# Si4356-V1.net
KiCad netlist of a schematic drawn in EAGLE
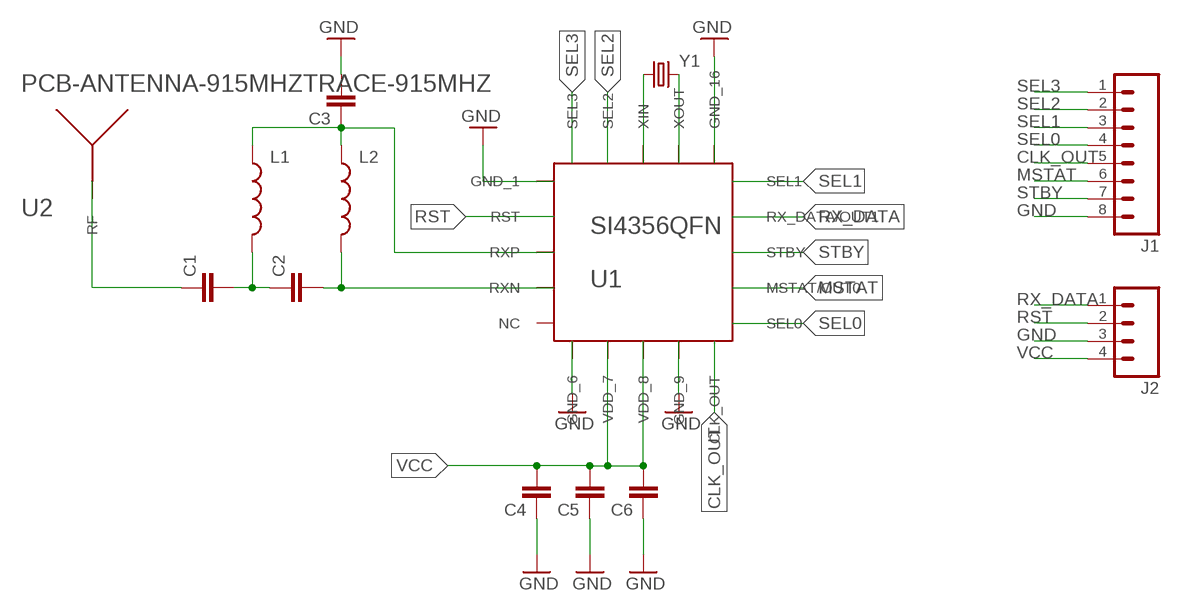
[diagram p0: schematic, sheet 1]

(export (version "E")
  (design (tool "Eeschema 10.0.6"))
  (components
    (comp (ref "C1")
      (value "CAP0603-CAP")
      (footprint "eagle-import:0603-CAP")
      (libsource (lib "eagle-import") (part "CAP0603-CAP"))
    )
    (comp (ref "C2")
      (value "CAP0603-CAP")
      (footprint "eagle-import:0603-CAP")
      (libsource (lib "eagle-import") (part "CAP0603-CAP"))
    )
    (comp (ref "C3")
      (value "CAP0603-CAP")
      (footprint "eagle-import:0603-CAP")
      (libsource (lib "eagle-import") (part "CAP0603-CAP"))
    )
    (comp (ref "C4")
      (value "CAP0603-CAP")
      (footprint "eagle-import:0603-CAP")
      (libsource (lib "eagle-import") (part "CAP0603-CAP"))
    )
    (comp (ref "C5")
      (value "CAP0603-CAP")
      (footprint "eagle-import:0603-CAP")
      (libsource (lib "eagle-import") (part "CAP0603-CAP"))
    )
    (comp (ref "C6")
      (value "CAP0603-CAP")
      (footprint "eagle-import:0603-CAP")
      (libsource (lib "eagle-import") (part "CAP0603-CAP"))
    )
    (comp (ref "J1")
      (value "M08")
      (footprint "eagle-import:1X08_ROUND")
      (libsource (lib "eagle-import") (part "M08"))
    )
    (comp (ref "J2")
      (value "M04PTH")
      (footprint "eagle-import:1X04")
      (libsource (lib "eagle-import") (part "M04PTH"))
    )
    (comp (ref "L1")
      (value "INDUCTOR0805")
      (footprint "eagle-import:0805")
      (libsource (lib "eagle-import") (part "INDUCTOR0805"))
    )
    (comp (ref "L2")
      (value "INDUCTOR0805")
      (footprint "eagle-import:0805")
      (libsource (lib "eagle-import") (part "INDUCTOR0805"))
    )
    (comp (ref "U1")
      (value "SI4356QFN")
      (footprint "eagle-import:QFN20-3X3MM")
      (libsource (lib "eagle-import") (part "SI4356QFN"))
    )
    (comp (ref "U2")
      (value "PCB-ANTENNA-915MHZTRACE-915MHZ")
      (footprint "eagle-import:PCB-ANTENNA-915MHZ-16.8MM")
      (libsource (lib "eagle-import") (part "PCB-ANTENNA-915MHZTRACE-915MHZ"))
    )
    (comp (ref "Y1")
      (value "CRYSTALHC49US")
      (footprint "eagle-import:HC49US")
      (libsource (lib "eagle-import") (part "CRYSTALHC49US"))
    )
  )
  (nets
    (net (code "1") (name "CLK_OUT") (class "Default")
      (node (ref "J1") (pin "5") (pinfunction "5_5") (pintype "passive"))
      (node (ref "U1") (pin "10") (pinfunction "CLK_OUT_10") (pintype "bidirectional"))
    )
    (net (code "2") (name "GND") (class "Default")
      (node (ref "C3") (pin "2") (pinfunction "2_2") (pintype "passive"))
      (node (ref "C4") (pin "1") (pinfunction "1_1") (pintype "passive"))
      (node (ref "C5") (pin "1") (pinfunction "1_1") (pintype "passive"))
      (node (ref "C6") (pin "1") (pinfunction "1_1") (pintype "passive"))
      (node (ref "J1") (pin "8") (pinfunction "8_8") (pintype "passive"))
      (node (ref "J2") (pin "3") (pinfunction "3_3") (pintype "passive"))
      (node (ref "U1") (pin "1") (pinfunction "GND_1_1") (pintype "power_in"))
      (node (ref "U1") (pin "16") (pinfunction "GND_16_16") (pintype "power_in"))
      (node (ref "U1") (pin "6") (pinfunction "GND_6_6") (pintype "bidirectional"))
      (node (ref "U1") (pin "9") (pinfunction "GND_9_9") (pintype "power_in"))
    )
    (net (code "3") (name "MSTAT") (class "Default")
      (node (ref "J1") (pin "6") (pinfunction "6_6") (pintype "passive"))
      (node (ref "U1") (pin "12") (pinfunction "MSTAT/OUT0_12") (pintype "bidirectional"))
    )
    (net (code "4") (name "Net-(C1-Pad2)") (class "Default")
      (node (ref "C1") (pin "2") (pinfunction "2_2") (pintype "passive"))
      (node (ref "C2") (pin "1") (pinfunction "1_1") (pintype "passive"))
      (node (ref "L1") (pin "2") (pinfunction "2_2") (pintype "passive"))
    )
    (net (code "5") (name "Net-(U1-RXN)") (class "Default")
      (node (ref "C2") (pin "2") (pinfunction "2_2") (pintype "passive"))
      (node (ref "L2") (pin "2") (pinfunction "2_2") (pintype "passive"))
      (node (ref "U1") (pin "4") (pinfunction "RXN_4") (pintype "bidirectional"))
    )
    (net (code "6") (name "Net-(U1-RXP)") (class "Default")
      (node (ref "C3") (pin "1") (pinfunction "1_1") (pintype "passive"))
      (node (ref "L1") (pin "1") (pinfunction "1_1") (pintype "passive"))
      (node (ref "L2") (pin "1") (pinfunction "1_1") (pintype "passive"))
      (node (ref "U1") (pin "3") (pinfunction "RXP_3") (pintype "bidirectional"))
    )
    (net (code "7") (name "Net-(U1-XIN)") (class "Default")
      (node (ref "U1") (pin "18") (pinfunction "XIN_18") (pintype "bidirectional"))
      (node (ref "Y1") (pin "1") (pinfunction "1_1") (pintype "passive"))
    )
    (net (code "8") (name "Net-(U1-XOUT)") (class "Default")
      (node (ref "U1") (pin "17") (pinfunction "XOUT_17") (pintype "bidirectional"))
      (node (ref "Y1") (pin "2") (pinfunction "2_2") (pintype "passive"))
    )
    (net (code "9") (name "Net-(U2-RF)") (class "Default")
      (node (ref "C1") (pin "1") (pinfunction "1_1") (pintype "passive"))
      (node (ref "U2") (pin "1") (pinfunction "RF_1") (pintype "input"))
    )
    (net (code "10") (name "RST") (class "Default")
      (node (ref "J2") (pin "2") (pinfunction "2_2") (pintype "passive"))
      (node (ref "U1") (pin "2") (pinfunction "RST_2") (pintype "bidirectional"))
    )
    (net (code "11") (name "RX_DATA") (class "Default")
      (node (ref "J2") (pin "1") (pinfunction "1_1") (pintype "passive"))
      (node (ref "U1") (pin "14") (pinfunction "RX_DATA/OUT1_14") (pintype "bidirectional"))
    )
    (net (code "12") (name "SEL0") (class "Default")
      (node (ref "J1") (pin "4") (pinfunction "4_4") (pintype "passive"))
      (node (ref "U1") (pin "11") (pinfunction "SEL0_11") (pintype "bidirectional"))
    )
    (net (code "13") (name "SEL1") (class "Default")
      (node (ref "J1") (pin "3") (pinfunction "3_3") (pintype "passive"))
      (node (ref "U1") (pin "15") (pinfunction "SEL1_15") (pintype "bidirectional"))
    )
    (net (code "14") (name "SEL2") (class "Default")
      (node (ref "J1") (pin "2") (pinfunction "2_2") (pintype "passive"))
      (node (ref "U1") (pin "19") (pinfunction "SEL2_19") (pintype "bidirectional"))
    )
    (net (code "15") (name "SEL3") (class "Default")
      (node (ref "J1") (pin "1") (pinfunction "1_1") (pintype "passive"))
      (node (ref "U1") (pin "20") (pinfunction "SEL3_20") (pintype "bidirectional"))
    )
    (net (code "16") (name "STBY") (class "Default")
      (node (ref "J1") (pin "7") (pinfunction "7_7") (pintype "passive"))
      (node (ref "U1") (pin "13") (pinfunction "STBY_13") (pintype "bidirectional"))
    )
    (net (code "17") (name "VCC") (class "Default")
      (node (ref "C4") (pin "2") (pinfunction "2_2") (pintype "passive"))
      (node (ref "C5") (pin "2") (pinfunction "2_2") (pintype "passive"))
      (node (ref "C6") (pin "2") (pinfunction "2_2") (pintype "passive"))
      (node (ref "J2") (pin "4") (pinfunction "4_4") (pintype "passive"))
      (node (ref "U1") (pin "7") (pinfunction "VDD_7_7") (pintype "power_in"))
      (node (ref "U1") (pin "8") (pinfunction "VDD_8_8") (pintype "power_in"))
    )
    (net (code "18") (name "unconnected-(U1-NC-Pad5)") (class "Default")
      (node (ref "U1") (pin "5") (pinfunction "NC_5") (pintype "no_connect"))
    )
  )
)
